# 06cpu_soc.net
KiCad netlist of a schematic drawn in Altium Designer
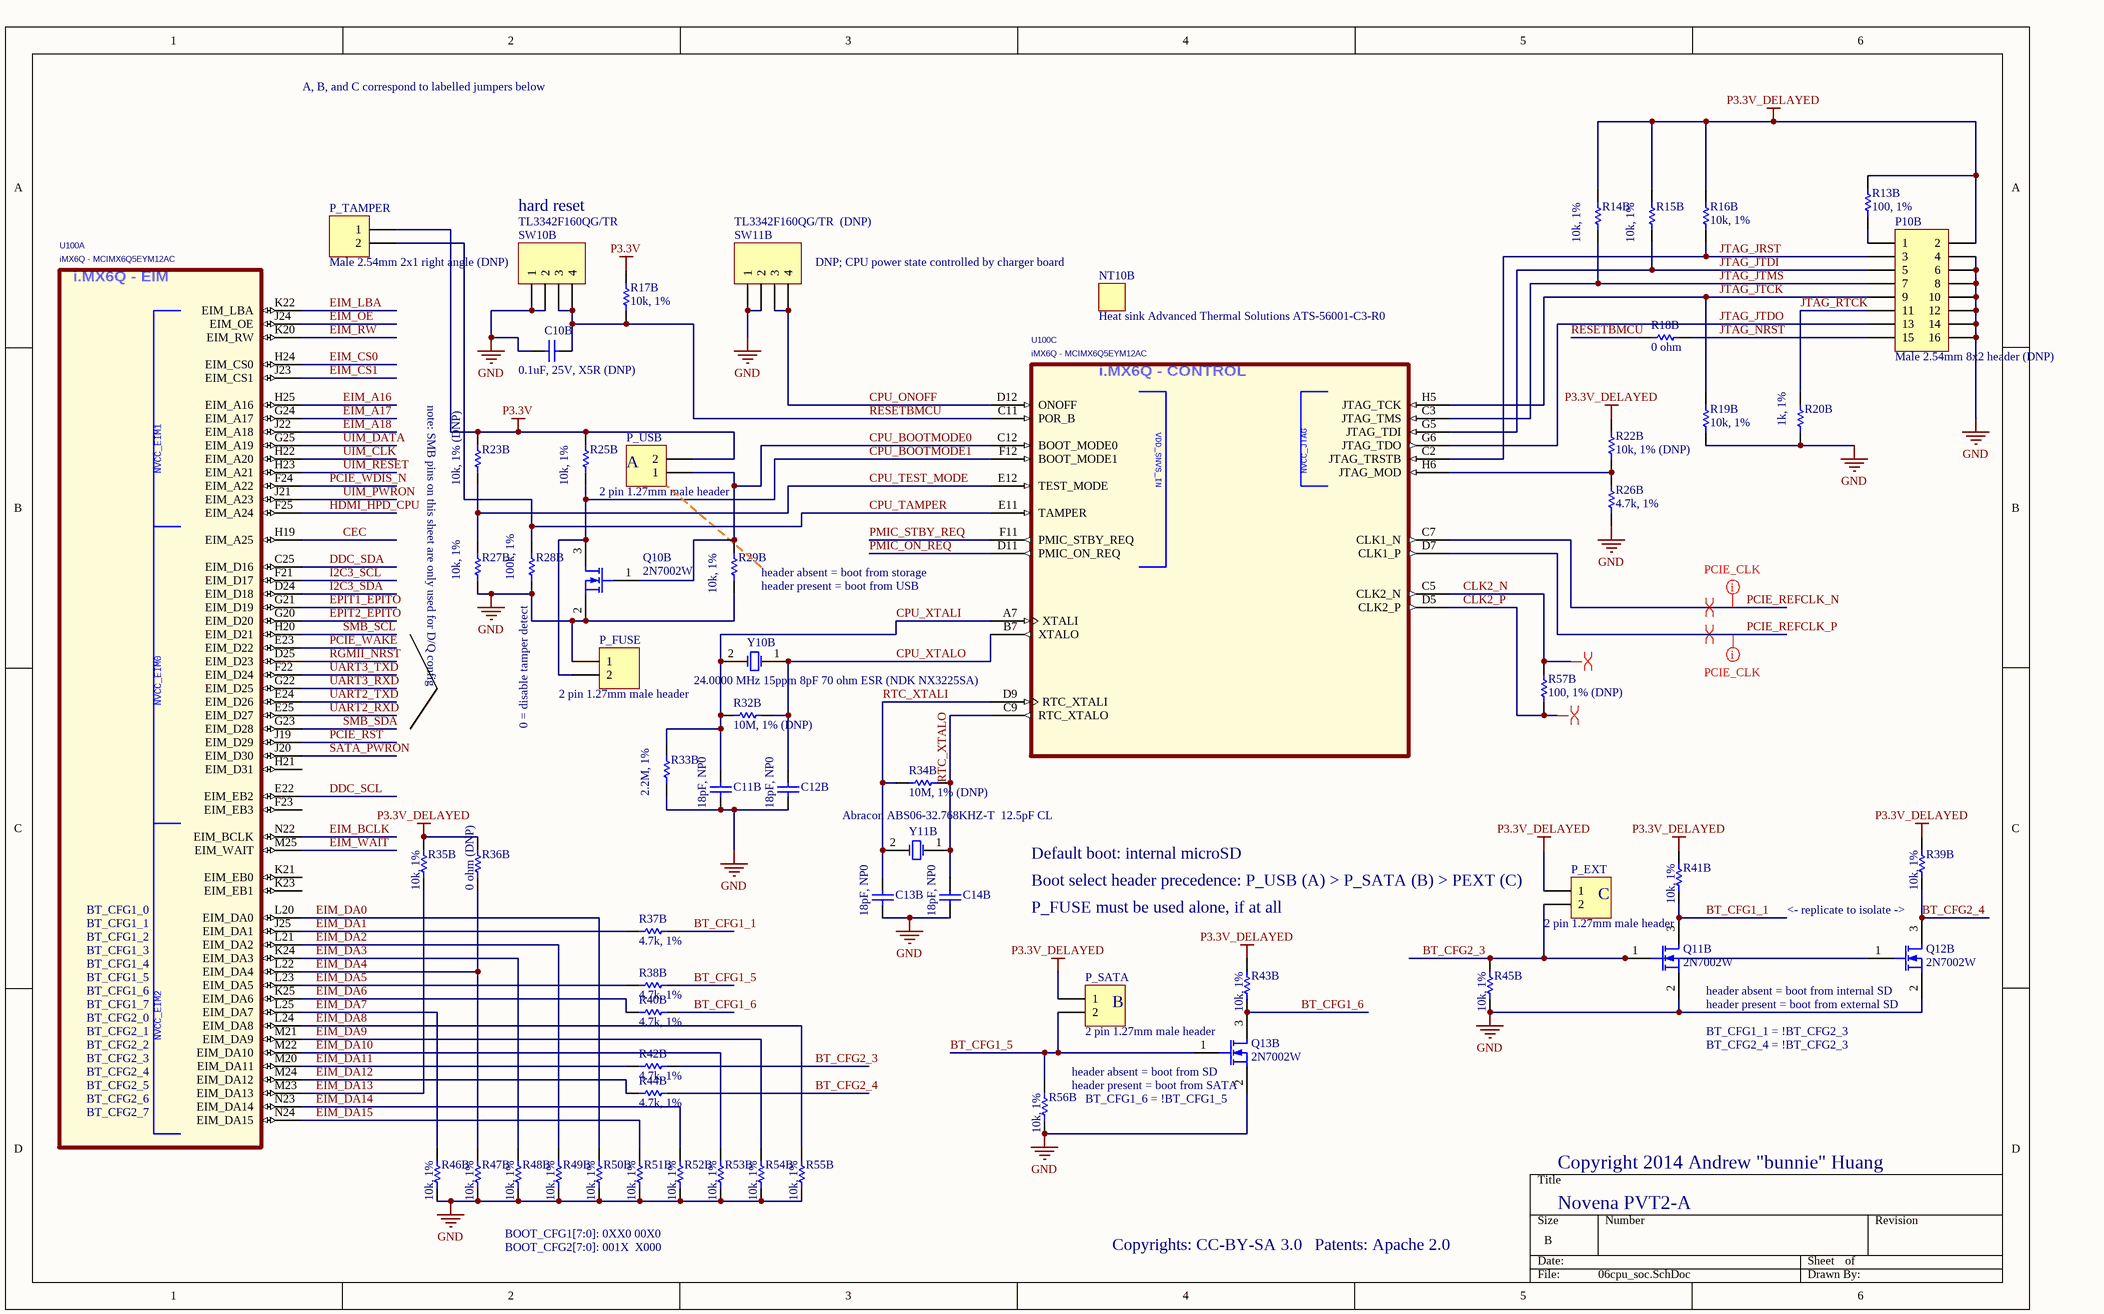
[diagram p0: 06cpu_soc.SchDoc]

(export (version "E")
  (design (tool "Eeschema 10.0.6"))
  (components
    (comp (ref "C10B")
      (value "0.1uF, 25V, X5R (DNP)")
      (footprint "CAPC1005N")
      (description "Capacitor (Semiconductor SIM Model)")
      (fields (field (name "PUBLISHER") "Altium Limited"))
      (libsource (lib "Miscellaneous Devices") (part "Cap Semi"))
    )
    (comp (ref "C11B")
      (value "18pF, NP0")
      (footprint "CAPC1005N")
      (description "Capacitor (Semiconductor SIM Model)")
      (fields (field (name "PUBLISHER") "Altium Limited"))
      (libsource (lib "Miscellaneous Devices") (part "Cap Semi"))
    )
    (comp (ref "C12B")
      (value "18pF, NP0")
      (footprint "CAPC1005N")
      (description "Capacitor (Semiconductor SIM Model)")
      (fields (field (name "PUBLISHER") "Altium Limited"))
      (libsource (lib "Miscellaneous Devices") (part "Cap Semi"))
    )
    (comp (ref "C13B")
      (value "18pF, NP0")
      (footprint "CAPC1005N")
      (description "Capacitor (Semiconductor SIM Model)")
      (fields (field (name "PUBLISHER") "Altium Limited"))
      (libsource (lib "Miscellaneous Devices") (part "Cap Semi"))
    )
    (comp (ref "C14B")
      (value "18pF, NP0")
      (footprint "CAPC1005N")
      (description "Capacitor (Semiconductor SIM Model)")
      (fields (field (name "PUBLISHER") "Altium Limited"))
      (libsource (lib "Miscellaneous Devices") (part "Cap Semi"))
    )
    (comp (ref "NT10B")
      (value "Heat sink Advanced Thermal Solutions ATS-56001-C3-R0")
      (description "Placeholder for non-electrical BOM items")
      (libsource (lib "commonsch") (part "NOTE"))
    )
    (comp (ref "P10B")
      (value "Male 2.54mm 8x2 header (DNP)")
      (footprint "HDR2X8")
      (description "Header, 8-Pin, Dual row")
      (fields (field (name "PUBLISHER") "Altium Limited"))
      (libsource (lib "Miscellaneous Connectors") (part "Header 8X2"))
    )
    (comp (ref "P_EXT")
      (value "2 pin 1.27mm male header")
      (footprint "HEADER_2_1.27MM")
      (description "Header, 2-Pin")
      (fields (field (name "PUBLISHER") "Altium Limited"))
      (libsource (lib "") (part "Header 2_1"))
    )
    (comp (ref "P_FUSE")
      (value "2 pin 1.27mm male header")
      (footprint "HEADER_2_1.27MM")
      (description "Header, 2-Pin")
      (fields (field (name "PUBLISHER") "Altium Limited"))
      (libsource (lib "") (part "Header 2_1"))
    )
    (comp (ref "P_SATA")
      (value "2 pin 1.27mm male header")
      (footprint "HEADER_2_1.27MM")
      (description "Header, 2-Pin")
      (fields (field (name "PUBLISHER") "Altium Limited"))
      (libsource (lib "") (part "Header 2_1"))
    )
    (comp (ref "P_TAMPER")
      (value "Male 2.54mm 2x1 right angle (DNP)")
      (footprint "HDR1X2H")
      (description "Header, 2-Pin, Right Angle")
      (fields (field (name "PUBLISHER") "Altium Limited"))
      (libsource (lib "Miscellaneous Connectors") (part "Header 2H"))
    )
    (comp (ref "P_USB")
      (value "2 pin 1.27mm male header")
      (footprint "HEADER_2_1.27MM")
      (description "Header, 2-Pin")
      (fields (field (name "PUBLISHER") "Altium Limited"))
      (libsource (lib "Miscellaneous Connectors") (part "Header 2"))
    )
    (comp (ref "Q10B")
      (value "2N7002W")
      (footprint "SOT323-3AN")
      (description "N-Channel MOSFET")
      (fields (field (name "PUBLISHER") "Altium Limited"))
      (libsource (lib "Miscellaneous Devices") (part "MOSFET-N"))
    )
    (comp (ref "Q11B")
      (value "2N7002W")
      (footprint "SOT323-3AN")
      (description "N-Channel MOSFET")
      (fields (field (name "PUBLISHER") "Altium Limited"))
      (libsource (lib "Miscellaneous Devices") (part "MOSFET-N"))
    )
    (comp (ref "Q12B")
      (value "2N7002W")
      (footprint "SOT323-3AN")
      (description "N-Channel MOSFET")
      (fields (field (name "PUBLISHER") "Altium Limited"))
      (libsource (lib "Miscellaneous Devices") (part "MOSFET-N"))
    )
    (comp (ref "Q13B")
      (value "2N7002W")
      (footprint "SOT323-3AN")
      (description "N-Channel MOSFET")
      (fields (field (name "PUBLISHER") "Altium Limited"))
      (libsource (lib "Miscellaneous Devices") (part "MOSFET-N"))
    )
    (comp (ref "R13B")
      (value "100, 1%")
      (footprint "RESC1005N")
      (description "Resistor")
      (fields (field (name "PUBLISHER") "Altium Limited"))
      (libsource (lib "Miscellaneous Devices") (part "Res1"))
    )
    (comp (ref "R14B")
      (value "10k, 1%")
      (footprint "RESC1005N")
      (description "Resistor")
      (fields (field (name "PUBLISHER") "Altium Limited"))
      (libsource (lib "Miscellaneous Devices") (part "Res1"))
    )
    (comp (ref "R15B")
      (value "10k, 1%")
      (footprint "RESC1005N")
      (description "Resistor")
      (fields (field (name "PUBLISHER") "Altium Limited"))
      (libsource (lib "Miscellaneous Devices") (part "Res1"))
    )
    (comp (ref "R16B")
      (value "10k, 1%")
      (footprint "RESC1005N")
      (description "Resistor")
      (fields (field (name "PUBLISHER") "Altium Limited"))
      (libsource (lib "Miscellaneous Devices") (part "Res1"))
    )
    (comp (ref "R17B")
      (value "10k, 1%")
      (footprint "RESC1005N")
      (description "Resistor")
      (fields (field (name "PUBLISHER") "Altium Limited"))
      (libsource (lib "Miscellaneous Devices") (part "Res1"))
    )
    (comp (ref "R18B")
      (value "0 ohm")
      (footprint "RESC1005N")
      (description "Resistor")
      (fields (field (name "PUBLISHER") "Altium Limited"))
      (libsource (lib "Miscellaneous Devices") (part "Res1"))
    )
    (comp (ref "R19B")
      (value "10k, 1%")
      (footprint "RESC1005N")
      (description "Resistor")
      (fields (field (name "PUBLISHER") "Altium Limited"))
      (libsource (lib "Miscellaneous Devices") (part "Res1"))
    )
    (comp (ref "R20B")
      (value "1k, 1%")
      (footprint "RESC1005N")
      (description "Resistor")
      (fields (field (name "PUBLISHER") "Altium Limited"))
      (libsource (lib "Miscellaneous Devices") (part "Res1"))
    )
    (comp (ref "R22B")
      (value "10k, 1% (DNP)")
      (footprint "RESC1005N")
      (description "Resistor")
      (fields (field (name "PUBLISHER") "Altium Limited"))
      (libsource (lib "Miscellaneous Devices") (part "Res1"))
    )
    (comp (ref "R23B")
      (value "10k, 1% (DNP)")
      (footprint "RESC1005N")
      (description "Resistor")
      (fields (field (name "PUBLISHER") "Altium Limited"))
      (libsource (lib "Miscellaneous Devices") (part "Res1"))
    )
    (comp (ref "R25B")
      (value "10k, 1%")
      (footprint "RESC1005N")
      (description "Resistor")
      (fields (field (name "PUBLISHER") "Altium Limited"))
      (libsource (lib "Miscellaneous Devices") (part "Res1"))
    )
    (comp (ref "R26B")
      (value "4.7k, 1%")
      (footprint "RESC1005N")
      (description "Resistor")
      (fields (field (name "PUBLISHER") "Altium Limited"))
      (libsource (lib "Miscellaneous Devices") (part "Res1"))
    )
    (comp (ref "R27B")
      (value "10k, 1%")
      (footprint "RESC1005N")
      (description "Resistor")
      (fields (field (name "PUBLISHER") "Altium Limited"))
      (libsource (lib "Miscellaneous Devices") (part "Res1"))
    )
    (comp (ref "R28B")
      (value "100k, 1%")
      (footprint "RESC1005N")
      (description "Resistor")
      (fields (field (name "PUBLISHER") "Altium Limited"))
      (libsource (lib "Miscellaneous Devices") (part "Res1"))
    )
    (comp (ref "R29B")
      (value "10k, 1%")
      (footprint "RESC1005N")
      (description "Resistor")
      (fields (field (name "PUBLISHER") "Altium Limited"))
      (libsource (lib "Miscellaneous Devices") (part "Res1"))
    )
    (comp (ref "R32B")
      (value "10M, 1% (DNP)")
      (footprint "RESC1005N")
      (description "Resistor")
      (fields (field (name "PUBLISHER") "Altium Limited"))
      (libsource (lib "Miscellaneous Devices") (part "Res1"))
    )
    (comp (ref "R33B")
      (value "2.2M, 1%")
      (footprint "RESC1005N")
      (description "Resistor")
      (fields (field (name "PUBLISHER") "Altium Limited"))
      (libsource (lib "Miscellaneous Devices") (part "Res1"))
    )
    (comp (ref "R34B")
      (value "10M, 1% (DNP)")
      (footprint "RESC1005N")
      (description "Resistor")
      (fields (field (name "PUBLISHER") "Altium Limited"))
      (libsource (lib "Miscellaneous Devices") (part "Res1"))
    )
    (comp (ref "R35B")
      (value "10k, 1%")
      (footprint "RESC1005N")
      (description "Resistor")
      (fields (field (name "PUBLISHER") "Altium Limited"))
      (libsource (lib "Miscellaneous Devices") (part "Res1"))
    )
    (comp (ref "R36B")
      (value "0 ohm (DNP)")
      (footprint "RESC1005N")
      (description "Resistor")
      (fields (field (name "PUBLISHER") "Altium Limited"))
      (libsource (lib "Miscellaneous Devices") (part "Res1"))
    )
    (comp (ref "R37B")
      (value "4.7k, 1%")
      (footprint "RESC1005N")
      (description "Resistor")
      (fields (field (name "PUBLISHER") "Altium Limited"))
      (libsource (lib "Miscellaneous Devices") (part "Res1"))
    )
    (comp (ref "R38B")
      (value "4.7k, 1%")
      (footprint "RESC1005N")
      (description "Resistor")
      (fields (field (name "PUBLISHER") "Altium Limited"))
      (libsource (lib "Miscellaneous Devices") (part "Res1"))
    )
    (comp (ref "R39B")
      (value "10k, 1%")
      (footprint "RESC1005N")
      (description "Resistor")
      (fields (field (name "PUBLISHER") "Altium Limited"))
      (libsource (lib "Miscellaneous Devices") (part "Res1"))
    )
    (comp (ref "R40B")
      (value "4.7k, 1%")
      (footprint "RESC1005N")
      (description "Resistor")
      (fields (field (name "PUBLISHER") "Altium Limited"))
      (libsource (lib "Miscellaneous Devices") (part "Res1"))
    )
    (comp (ref "R41B")
      (value "10k, 1%")
      (footprint "RESC1005N")
      (description "Resistor")
      (fields (field (name "PUBLISHER") "Altium Limited"))
      (libsource (lib "Miscellaneous Devices") (part "Res1"))
    )
    (comp (ref "R42B")
      (value "4.7k, 1%")
      (footprint "RESC1005N")
      (description "Resistor")
      (fields (field (name "PUBLISHER") "Altium Limited"))
      (libsource (lib "Miscellaneous Devices") (part "Res1"))
    )
    (comp (ref "R43B")
      (value "10k, 1%")
      (footprint "RESC1005N")
      (description "Resistor")
      (fields (field (name "PUBLISHER") "Altium Limited"))
      (libsource (lib "Miscellaneous Devices") (part "Res1"))
    )
    (comp (ref "R44B")
      (value "4.7k, 1%")
      (footprint "RESC1005N")
      (description "Resistor")
      (fields (field (name "PUBLISHER") "Altium Limited"))
      (libsource (lib "Miscellaneous Devices") (part "Res1"))
    )
    (comp (ref "R45B")
      (value "10k, 1%")
      (footprint "RESC1005N")
      (description "Resistor")
      (fields (field (name "PUBLISHER") "Altium Limited"))
      (libsource (lib "Miscellaneous Devices") (part "Res1"))
    )
    (comp (ref "R46B")
      (value "10k, 1%")
      (footprint "RESC1005N")
      (description "Resistor")
      (fields (field (name "PUBLISHER") "Altium Limited"))
      (libsource (lib "Miscellaneous Devices") (part "Res1"))
    )
    (comp (ref "R47B")
      (value "10k, 1%")
      (footprint "RESC1005N")
      (description "Resistor")
      (fields (field (name "PUBLISHER") "Altium Limited"))
      (libsource (lib "Miscellaneous Devices") (part "Res1"))
    )
    (comp (ref "R48B")
      (value "10k, 1%")
      (footprint "RESC1005N")
      (description "Resistor")
      (fields (field (name "PUBLISHER") "Altium Limited"))
      (libsource (lib "Miscellaneous Devices") (part "Res1"))
    )
    (comp (ref "R49B")
      (value "10k, 1%")
      (footprint "RESC1005N")
      (description "Resistor")
      (fields (field (name "PUBLISHER") "Altium Limited"))
      (libsource (lib "Miscellaneous Devices") (part "Res1"))
    )
    (comp (ref "R50B")
      (value "10k, 1%")
      (footprint "RESC1005N")
      (description "Resistor")
      (fields (field (name "PUBLISHER") "Altium Limited"))
      (libsource (lib "Miscellaneous Devices") (part "Res1"))
    )
    (comp (ref "R51B")
      (value "10k, 1%")
      (footprint "RESC1005N")
      (description "Resistor")
      (fields (field (name "PUBLISHER") "Altium Limited"))
      (libsource (lib "Miscellaneous Devices") (part "Res1"))
    )
    (comp (ref "R52B")
      (value "10k, 1%")
      (footprint "RESC1005N")
      (description "Resistor")
      (fields (field (name "PUBLISHER") "Altium Limited"))
      (libsource (lib "Miscellaneous Devices") (part "Res1"))
    )
    (comp (ref "R53B")
      (value "10k, 1%")
      (footprint "RESC1005N")
      (description "Resistor")
      (fields (field (name "PUBLISHER") "Altium Limited"))
      (libsource (lib "Miscellaneous Devices") (part "Res1"))
    )
    (comp (ref "R54B")
      (value "10k, 1%")
      (footprint "RESC1005N")
      (description "Resistor")
      (fields (field (name "PUBLISHER") "Altium Limited"))
      (libsource (lib "Miscellaneous Devices") (part "Res1"))
    )
    (comp (ref "R55B")
      (value "10k, 1%")
      (footprint "RESC1005N")
      (description "Resistor")
      (fields (field (name "PUBLISHER") "Altium Limited"))
      (libsource (lib "Miscellaneous Devices") (part "Res1"))
    )
    (comp (ref "R56B")
      (value "10k, 1%")
      (footprint "RESC1005N")
      (description "Resistor")
      (fields (field (name "PUBLISHER") "Altium Limited"))
      (libsource (lib "Miscellaneous Devices") (part "Res1"))
    )
    (comp (ref "R57B")
      (value "100, 1% (DNP)")
      (footprint "RESC1005N")
      (description "Resistor")
      (fields (field (name "PUBLISHER") "Altium Limited"))
      (libsource (lib "Miscellaneous Devices") (part "Res1"))
    )
    (comp (ref "SW10B")
      (value "TL3342F160QG/TR")
      (footprint "SWITCH_TS-1187A")
      (description "Chi Fung TS-1187A")
      (fields (field (name "PUBLISHER") "Altium Limited"))
      (libsource (lib "Miscellaneous Connectors") (part "Header 4"))
    )
    (comp (ref "SW11B")
      (value "TL3342F160QG/TR  (DNP)")
      (footprint "SWITCH_TS-1187A")
      (description "Chi Fung TS-1187A")
      (fields (field (name "PUBLISHER") "Altium Limited"))
      (libsource (lib "Miscellaneous Connectors") (part "Header 4"))
    )
    (comp (ref "U100")
      (value "iMX6Q - MCIMX6Q5EYM12AC")
      (description "PCIMX6Q5EVT10AC")
      (libsource (lib "*") (part "PCIMX6Q6VV1A"))
    )
    (comp (ref "Y10B")
      (value "24.0000 MHz 15ppm 8pF 70 ohm ESR (NDK NX3225SA)")
      (footprint "NDK_NX3225SA")
      (description "Crystal Oscillator")
      (fields (field (name "PUBLISHER") "Altium Limited"))
      (libsource (lib "Miscellaneous Devices") (part "XTAL"))
    )
    (comp (ref "Y11B")
      (value "Abracon ABS06-32.768KHZ-T  12.5pF CL")
      (footprint "ABS06")
      (description "Crystal Oscillator")
      (fields (field (name "PUBLISHER") "Altium Limited"))
      (libsource (lib "Miscellaneous Devices") (part "XTAL"))
    )
  )
  (nets
    (net (code "1") (name "/BT_CFG1_1") (class "Default")
      (node (ref "Q11B") (pin "3") (pinfunction "D_3") (pintype "passive"))
      (node (ref "R37B") (pin "2") (pinfunction "2_2") (pintype "passive"))
      (node (ref "R41B") (pin "2") (pinfunction "2_2") (pintype "passive"))
    )
    (net (code "2") (name "/BT_CFG1_5") (class "Default")
      (node (ref "P_SATA") (pin "2") (pinfunction "2_2") (pintype "passive"))
      (node (ref "Q13B") (pin "1") (pinfunction "G_1") (pintype "passive"))
      (node (ref "R38B") (pin "2") (pinfunction "2_2") (pintype "passive"))
      (node (ref "R56B") (pin "1") (pinfunction "1_1") (pintype "passive"))
    )
    (net (code "3") (name "/BT_CFG1_6") (class "Default")
      (node (ref "Q13B") (pin "3") (pinfunction "D_3") (pintype "passive"))
      (node (ref "R40B") (pin "2") (pinfunction "2_2") (pintype "passive"))
      (node (ref "R43B") (pin "2") (pinfunction "2_2") (pintype "passive"))
    )
    (net (code "4") (name "/BT_CFG2_3") (class "Default")
      (node (ref "P_EXT") (pin "2") (pinfunction "2_2") (pintype "passive"))
      (node (ref "Q11B") (pin "1") (pinfunction "G_1") (pintype "passive"))
      (node (ref "Q12B") (pin "1") (pinfunction "G_1") (pintype "passive"))
      (node (ref "R42B") (pin "2") (pinfunction "2_2") (pintype "passive"))
      (node (ref "R45B") (pin "1") (pinfunction "1_1") (pintype "passive"))
    )
    (net (code "5") (name "/BT_CFG2_4") (class "Default")
      (node (ref "Q12B") (pin "3") (pinfunction "D_3") (pintype "passive"))
      (node (ref "R39B") (pin "2") (pinfunction "2_2") (pintype "passive"))
      (node (ref "R44B") (pin "2") (pinfunction "2_2") (pintype "passive"))
    )
    (net (code "6") (name "/CEC") (class "Default")
      (node (ref "U100") (pin "H19") (pinfunction "EIM_A25_H19") (pintype "bidirectional"))
    )
    (net (code "7") (name "/CLK2_N") (class "Default")
      (node (ref "R57B") (pin "2") (pinfunction "2_2") (pintype "passive"))
      (node (ref "U100") (pin "C5") (pinfunction "CLK2_N_C5") (pintype "output"))
    )
    (net (code "8") (name "/CLK2_P") (class "Default")
      (node (ref "R57B") (pin "1") (pinfunction "1_1") (pintype "passive"))
      (node (ref "U100") (pin "D5") (pinfunction "CLK2_P_D5") (pintype "output"))
    )
    (net (code "9") (name "/CPU_BOOTMODE0") (class "Default")
      (node (ref "P_USB") (pin "1") (pinfunction "1_1") (pintype "passive"))
      (node (ref "Q10B") (pin "1") (pinfunction "G_1") (pintype "passive"))
      (node (ref "R29B") (pin "2") (pinfunction "2_2") (pintype "passive"))
      (node (ref "U100") (pin "C12") (pinfunction "BOOT_MODE0_C12") (pintype "input"))
    )
    (net (code "10") (name "/CPU_BOOTMODE1") (class "Default")
      (node (ref "P_FUSE") (pin "2") (pinfunction "2_2") (pintype "passive"))
      (node (ref "Q10B") (pin "3") (pinfunction "D_3") (pintype "passive"))
      (node (ref "R25B") (pin "1") (pinfunction "1_1") (pintype "passive"))
      (node (ref "U100") (pin "F12") (pinfunction "BOOT_MODE1_F12") (pintype "input"))
    )
    (net (code "11") (name "/CPU_ONOFF") (class "Default")
      (node (ref "SW11B") (pin "3") (pinfunction "3_3") (pintype "passive"))
      (node (ref "SW11B") (pin "4") (pinfunction "4_4") (pintype "passive"))
      (node (ref "U100") (pin "D12") (pinfunction "ONOFF_D12") (pintype "input"))
    )
    (net (code "12") (name "/CPU_TAMPER") (class "Default")
      (node (ref "P_TAMPER") (pin "2") (pinfunction "2_2") (pintype "passive"))
      (node (ref "R28B") (pin "2") (pinfunction "2_2") (pintype "passive"))
      (node (ref "U100") (pin "E11") (pinfunction "TAMPER_E11") (pintype "input"))
    )
    (net (code "13") (name "/CPU_TEST_MODE") (class "Default")
      (node (ref "R23B") (pin "1") (pinfunction "1_1") (pintype "passive"))
      (node (ref "R27B") (pin "2") (pinfunction "2_2") (pintype "passive"))
      (node (ref "U100") (pin "E12") (pinfunction "TEST_MODE_E12") (pintype "input"))
    )
    (net (code "14") (name "/CPU_XTALI") (class "Default")
      (node (ref "C11B") (pin "1") (pinfunction "1_1") (pintype "passive"))
      (node (ref "R32B") (pin "1") (pinfunction "1_1") (pintype "passive"))
      (node (ref "R33B") (pin "1") (pinfunction "1_1") (pintype "passive"))
      (node (ref "U100") (pin "A7") (pinfunction "XTALI_A7") (pintype "input"))
      (node (ref "Y10B") (pin "2") (pinfunction "OSC2_2") (pintype "passive"))
    )
    (net (code "15") (name "/CPU_XTALO") (class "Default")
      (node (ref "C12B") (pin "1") (pinfunction "1_1") (pintype "passive"))
      (node (ref "R32B") (pin "2") (pinfunction "2_2") (pintype "passive"))
      (node (ref "U100") (pin "B7") (pinfunction "XTALO_B7") (pintype "output"))
      (node (ref "Y10B") (pin "1") (pinfunction "OSC1_1") (pintype "passive"))
    )
    (net (code "16") (name "/DDC_SCL") (class "Default")
      (node (ref "U100") (pin "E22") (pinfunction "EIM_EB2_E22") (pintype "bidirectional"))
    )
    (net (code "17") (name "/DDC_SDA") (class "Default")
      (node (ref "U100") (pin "C25") (pinfunction "EIM_D16_C25") (pintype "bidirectional"))
    )
    (net (code "18") (name "/EIM_A16") (class "Default")
      (node (ref "U100") (pin "H25") (pinfunction "EIM_A16_H25") (pintype "bidirectional"))
    )
    (net (code "19") (name "/EIM_A17") (class "Default")
      (node (ref "U100") (pin "G24") (pinfunction "EIM_A17_G24") (pintype "bidirectional"))
    )
    (net (code "20") (name "/EIM_A18") (class "Default")
      (node (ref "U100") (pin "J22") (pinfunction "EIM_A18_J22") (pintype "bidirectional"))
    )
    (net (code "21") (name "/EIM_BCLK") (class "Default")
      (node (ref "U100") (pin "N22") (pinfunction "EIM_BCLK_N22") (pintype "bidirectional"))
    )
    (net (code "22") (name "/EIM_CS0") (class "Default")
      (node (ref "U100") (pin "H24") (pinfunction "EIM_CS0_H24") (pintype "bidirectional"))
    )
    (net (code "23") (name "/EIM_CS1") (class "Default")
      (node (ref "U100") (pin "J23") (pinfunction "EIM_CS1_J23") (pintype "bidirectional"))
    )
    (net (code "24") (name "/EIM_DA0") (class "Default")
      (node (ref "R50B") (pin "1") (pinfunction "1_1") (pintype "passive"))
      (node (ref "U100") (pin "L20") (pinfunction "EIM_DA0_L20") (pintype "bidirectional"))
    )
    (net (code "25") (name "/EIM_DA1") (class "Default")
      (node (ref "R37B") (pin "1") (pinfunction "1_1") (pintype "passive"))
      (node (ref "U100") (pin "J25") (pinfunction "EIM_DA1_J25") (pintype "bidirectional"))
    )
    (net (code "26") (name "/EIM_DA2") (class "Default")
      (node (ref "R49B") (pin "1") (pinfunction "1_1") (pintype "passive"))
      (node (ref "U100") (pin "L21") (pinfunction "EIM_DA2_L21") (pintype "bidirectional"))
    )
    (net (code "27") (name "/EIM_DA3") (class "Default")
      (node (ref "R48B") (pin "1") (pinfunction "1_1") (pintype "passive"))
      (node (ref "U100") (pin "K24") (pinfunction "EIM_DA3_K24") (pintype "bidirectional"))
    )
    (net (code "28") (name "/EIM_DA4") (class "Default")
      (node (ref "R36B") (pin "2") (pinfunction "2_2") (pintype "passive"))
      (node (ref "R47B") (pin "1") (pinfunction "1_1") (pintype "passive"))
      (node (ref "U100") (pin "L22") (pinfunction "EIM_DA4_L22") (pintype "bidirectional"))
    )
    (net (code "29") (name "/EIM_DA5") (class "Default")
      (node (ref "R38B") (pin "1") (pinfunction "1_1") (pintype "passive"))
      (node (ref "U100") (pin "L23") (pinfunction "EIM_DA5_L23") (pintype "bidirectional"))
    )
    (net (code "30") (name "/EIM_DA6") (class "Default")
      (node (ref "R40B") (pin "1") (pinfunction "1_1") (pintype "passive"))
      (node (ref "U100") (pin "K25") (pinfunction "EIM_DA6_K25") (pintype "bidirectional"))
    )
    (net (code "31") (name "/EIM_DA7") (class "Default")
      (node (ref "R46B") (pin "1") (pinfunction "1_1") (pintype "passive"))
      (node (ref "U100") (pin "L25") (pinfunction "EIM_DA7_L25") (pintype "bidirectional"))
    )
    (net (code "32") (name "/EIM_DA8") (class "Default")
      (node (ref "R55B") (pin "1") (pinfunction "1_1") (pintype "passive"))
      (node (ref "U100") (pin "L24") (pinfunction "EIM_DA8_L24") (pintype "bidirectional"))
    )
    (net (code "33") (name "/EIM_DA9") (class "Default")
      (node (ref "R54B") (pin "1") (pinfunction "1_1") (pintype "passive"))
      (node (ref "U100") (pin "M21") (pinfunction "EIM_DA9_M21") (pintype "bidirectional"))
    )
    (net (code "34") (name "/EIM_DA10") (class "Default")
      (node (ref "R53B") (pin "1") (pinfunction "1_1") (pintype "passive"))
      (node (ref "U100") (pin "M22") (pinfunction "EIM_DA10_M22") (pintype "bidirectional"))
    )
    (net (code "35") (name "/EIM_DA11") (class "Default")
      (node (ref "R42B") (pin "1") (pinfunction "1_1") (pintype "passive"))
      (node (ref "U100") (pin "M20") (pinfunction "EIM_DA11_M20") (pintype "bidirectional"))
    )
    (net (code "36") (name "/EIM_DA12") (class "Default")
      (node (ref "R44B") (pin "1") (pinfunction "1_1") (pintype "passive"))
      (node (ref "U100") (pin "M24") (pinfunction "EIM_DA12_M24") (pintype "bidirectional"))
    )
    (net (code "37") (name "/EIM_DA13") (class "Default")
      (node (ref "R35B") (pin "2") (pinfunction "2_2") (pintype "passive"))
      (node (ref "U100") (pin "M23") (pinfunction "EIM_DA13_M23") (pintype "bidirectional"))
    )
    (net (code "38") (name "/EIM_DA14") (class "Default")
      (node (ref "R52B") (pin "1") (pinfunction "1_1") (pintype "passive"))
      (node (ref "U100") (pin "N23") (pinfunction "EIM_DA14_N23") (pintype "bidirectional"))
    )
    (net (code "39") (name "/EIM_DA15") (class "Default")
      (node (ref "R51B") (pin "1") (pinfunction "1_1") (pintype "passive"))
      (node (ref "U100") (pin "N24") (pinfunction "EIM_DA15_N24") (pintype "bidirectional"))
    )
    (net (code "40") (name "/EIM_LBA") (class "Default")
      (node (ref "U100") (pin "K22") (pinfunction "EIM_LBA_K22") (pintype "bidirectional"))
    )
    (net (code "41") (name "/EIM_OE") (class "Default")
      (node (ref "U100") (pin "J24") (pinfunction "EIM_OE_J24") (pintype "bidirectional"))
    )
    (net (code "42") (name "/EIM_RW") (class "Default")
      (node (ref "U100") (pin "K20") (pinfunction "EIM_RW_K20") (pintype "bidirectional"))
    )
    (net (code "43") (name "/EIM_WAIT") (class "Default")
      (node (ref "U100") (pin "M25") (pinfunction "EIM_WAIT_M25") (pintype "bidirectional"))
    )
    (net (code "44") (name "/EPIT1_EPITO") (class "Default")
      (node (ref "U100") (pin "G21") (pinfunction "EIM_D19_G21") (pintype "bidirectional"))
    )
    (net (code "45") (name "/EPIT2_EPITO") (class "Default")
      (node (ref "U100") (pin "G20") (pinfunction "EIM_D20_G20") (pintype "bidirectional"))
    )
    (net (code "46") (name "/HDMI_HPD_CPU") (class "Default")
      (node (ref "U100") (pin "F25") (pinfunction "EIM_A24_F25") (pintype "bidirectional"))
    )
    (net (code "47") (name "/I2C3_SCL") (class "Default")
      (node (ref "U100") (pin "F21") (pinfunction "EIM_D17_F21") (pintype "bidirectional"))
    )
    (net (code "48") (name "/I2C3_SDA") (class "Default")
      (node (ref "U100") (pin "D24") (pinfunction "EIM_D18_D24") (pintype "bidirectional"))
    )
    (net (code "49") (name "/JTAG_JRST") (class "Default")
      (node (ref "P10B") (pin "3") (pinfunction "3_3") (pintype "passive"))
      (node (ref "R16B") (pin "1") (pinfunction "1_1") (pintype "passive"))
      (node (ref "U100") (pin "C2") (pinfunction "JTAG_TRSTB_C2") (pintype "input"))
    )
    (net (code "50") (name "/JTAG_JTCK") (class "Default")
      (node (ref "P10B") (pin "9") (pinfunction "9_9") (pintype "passive"))
      (node (ref "R19B") (pin "2") (pinfunction "2_2") (pintype "passive"))
      (node (ref "U100") (pin "H5") (pinfunction "JTAG_TCK_H5") (pintype "input"))
    )
    (net (code "51") (name "/JTAG_JTDI") (class "Default")
      (node (ref "P10B") (pin "5") (pinfunction "5_5") (pintype "passive"))
      (node (ref "R15B") (pin "1") (pinfunction "1_1") (pintype "passive"))
      (node (ref "U100") (pin "G5") (pinfunction "JTAG_TDI_G5") (pintype "input"))
    )
    (net (code "52") (name "/JTAG_JTDO") (class "Default")
      (node (ref "P10B") (pin "13") (pinfunction "13_13") (pintype "passive"))
      (node (ref "U100") (pin "G6") (pinfunction "JTAG_TDO_G6") (pintype "output"))
    )
    (net (code "53") (name "/JTAG_JTMS") (class "Default")
      (node (ref "P10B") (pin "7") (pinfunction "7_7") (pintype "passive"))
      (node (ref "R14B") (pin "1") (pinfunction "1_1") (pintype "passive"))
      (node (ref "U100") (pin "C3") (pinfunction "JTAG_TMS_C3") (pintype "input"))
    )
    (net (code "54") (name "/JTAG_NRST") (class "Default")
      (node (ref "P10B") (pin "15") (pinfunction "15_15") (pintype "passive"))
      (node (ref "R18B") (pin "1") (pinfunction "1_1") (pintype "passive"))
    )
    (net (code "55") (name "/JTAG_RTCK") (class "Default")
      (node (ref "P10B") (pin "11") (pinfunction "11_11") (pintype "passive"))
      (node (ref "R20B") (pin "2") (pinfunction "2_2") (pintype "passive"))
    )
    (net (code "56") (name "/PCIE_REFCLK_N") (class "Default")
      (node (ref "U100") (pin "C7") (pinfunction "CLK1_N_C7") (pintype "output"))
    )
    (net (code "57") (name "/PCIE_REFCLK_P") (class "Default")
      (node (ref "U100") (pin "D7") (pinfunction "CLK1_P_D7") (pintype "output"))
    )
    (net (code "58") (name "/PCIE_RST") (class "Default")
      (node (ref "U100") (pin "J19") (pinfunction "EIM_D29_J19") (pintype "bidirectional"))
    )
    (net (code "59") (name "/PCIE_WAKE") (class "Default")
      (node (ref "U100") (pin "E23") (pinfunction "EIM_D22_E23") (pintype "bidirectional"))
    )
    (net (code "60") (name "/PCIE_WDIS_N") (class "Default")
      (node (ref "U100") (pin "F24") (pinfunction "EIM_A22_F24") (pintype "bidirectional"))
    )
    (net (code "61") (name "/PMIC_ON_REQ") (class "Default")
      (node (ref "U100") (pin "D11") (pinfunction "PMIC_ON_REQ_D11") (pintype "output"))
    )
    (net (code "62") (name "/PMIC_STBY_REQ") (class "Default")
      (node (ref "U100") (pin "F11") (pinfunction "PMIC_STBY_REQ_F11") (pintype "output"))
    )
    (net (code "63") (name "/RESETBMCU") (class "Default")
      (node (ref "C10B") (pin "1") (pinfunction "1_1") (pintype "passive"))
      (node (ref "R17B") (pin "1") (pinfunction "1_1") (pintype "passive"))
      (node (ref "R18B") (pin "2") (pinfunction "2_2") (pintype "passive"))
      (node (ref "SW10B") (pin "3") (pinfunction "3_3") (pintype "passive"))
      (node (ref "SW10B") (pin "4") (pinfunction "4_4") (pintype "passive"))
      (node (ref "U100") (pin "C11") (pinfunction "POR_B_C11") (pintype "input"))
    )
    (net (code "64") (name "/RGMII_NRST") (class "Default")
      (node (ref "U100") (pin "D25") (pinfunction "EIM_D23_D25") (pintype "bidirectional"))
    )
    (net (code "65") (name "/RTC_XTALI") (class "Default")
      (node (ref "C13B") (pin "1") (pinfunction "1_1") (pintype "passive"))
      (node (ref "R34B") (pin "1") (pinfunction "1_1") (pintype "passive"))
      (node (ref "U100") (pin "D9") (pinfunction "RTC_XTALI_D9") (pintype "input"))
      (node (ref "Y11B") (pin "2") (pinfunction "OSC2_2") (pintype "passive"))
    )
    (net (code "66") (name "/RTC_XTALO") (class "Default")
      (node (ref "C14B") (pin "1") (pinfunction "1_1") (pintype "passive"))
      (node (ref "R34B") (pin "2") (pinfunction "2_2") (pintype "passive"))
      (node (ref "U100") (pin "C9") (pinfunction "RTC_XTALO_C9") (pintype "output"))
      (node (ref "Y11B") (pin "1") (pinfunction "OSC1_1") (pintype "passive"))
    )
    (net (code "67") (name "/SATA_PWRON") (class "Default")
      (node (ref "U100") (pin "J20") (pinfunction "EIM_D30_J20") (pintype "bidirectional"))
    )
    (net (code "68") (name "/SMB_SCL") (class "Default")
      (node (ref "U100") (pin "H20") (pinfunction "EIM_D21_H20") (pintype "bidirectional"))
    )
    (net (code "69") (name "/SMB_SDA") (class "Default")
      (node (ref "U100") (pin "G23") (pinfunction "EIM_D28_G23") (pintype "bidirectional"))
    )
    (net (code "70") (name "/UART2_RXD") (class "Default")
      (node (ref "U100") (pin "E25") (pinfunction "EIM_D27_E25") (pintype "bidirectional"))
    )
    (net (code "71") (name "/UART2_TXD") (class "Default")
      (node (ref "U100") (pin "E24") (pinfunction "EIM_D26_E24") (pintype "bidirectional"))
    )
    (net (code "72") (name "/UART3_RXD") (class "Default")
      (node (ref "U100") (pin "G22") (pinfunction "EIM_D25_G22") (pintype "bidirectional"))
    )
    (net (code "73") (name "/UART3_TXD") (class "Default")
      (node (ref "U100") (pin "F22") (pinfunction "EIM_D24_F22") (pintype "bidirectional"))
    )
    (net (code "74") (name "/UIM_CLK") (class "Default")
      (node (ref "U100") (pin "H22") (pinfunction "EIM_A20_H22") (pintype "bidirectional"))
    )
    (net (code "75") (name "/UIM_DATA") (class "Default")
      (node (ref "U100") (pin "G25") (pinfunction "EIM_A19_G25") (pintype "bidirectional"))
    )
    (net (code "76") (name "/UIM_PWRON") (class "Default")
      (node (ref "U100") (pin "J21") (pinfunction "EIM_A23_J21") (pintype "bidirectional"))
    )
    (net (code "77") (name "/UIM_RESET") (class "Default")
      (node (ref "U100") (pin "H23") (pinfunction "EIM_A21_H23") (pintype "bidirectional"))
    )
    (net (code "78") (name "GND") (class "Default")
      (node (ref "C10B") (pin "2") (pinfunction "2_2") (pintype "passive"))
      (node (ref "C11B") (pin "2") (pinfunction "2_2") (pintype "passive"))
      (node (ref "C12B") (pin "2") (pinfunction "2_2") (pintype "passive"))
      (node (ref "C13B") (pin "2") (pinfunction "2_2") (pintype "passive"))
      (node (ref "C14B") (pin "2") (pinfunction "2_2") (pintype "passive"))
      (node (ref "P10B") (pin "10") (pinfunction "10_10") (pintype "passive"))
      (node (ref "P10B") (pin "12") (pinfunction "12_12") (pintype "passive"))
      (node (ref "P10B") (pin "14") (pinfunction "14_14") (pintype "passive"))
      (node (ref "P10B") (pin "16") (pinfunction "16_16") (pintype "passive"))
      (node (ref "P10B") (pin "4") (pinfunction "4_4") (pintype "passive"))
      (node (ref "P10B") (pin "6") (pinfunction "6_6") (pintype "passive"))
      (node (ref "P10B") (pin "8") (pinfunction "8_8") (pintype "passive"))
      (node (ref "P_FUSE") (pin "1") (pinfunction "1_1") (pintype "passive"))
      (node (ref "Q10B") (pin "2") (pinfunction "S_2") (pintype "passive"))
      (node (ref "Q11B") (pin "2") (pinfunction "S_2") (pintype "passive"))
      (node (ref "Q12B") (pin "2") (pinfunction "S_2") (pintype "passive"))
      (node (ref "Q13B") (pin "2") (pinfunction "S_2") (pintype "passive"))
      (node (ref "R19B") (pin "1") (pinfunction "1_1") (pintype "passive"))
      (node (ref "R20B") (pin "1") (pinfunction "1_1") (pintype "passive"))
      (node (ref "R26B") (pin "1") (pinfunction "1_1") (pintype "passive"))
      (node (ref "R27B") (pin "1") (pinfunction "1_1") (pintype "passive"))
      (node (ref "R28B") (pin "1") (pinfunction "1_1") (pintype "passive"))
      (node (ref "R29B") (pin "1") (pinfunction "1_1") (pintype "passive"))
      (node (ref "R33B") (pin "2") (pinfunction "2_2") (pintype "passive"))
      (node (ref "R45B") (pin "2") (pinfunction "2_2") (pintype "passive"))
      (node (ref "R46B") (pin "2") (pinfunction "2_2") (pintype "passive"))
      (node (ref "R47B") (pin "2") (pinfunction "2_2") (pintype "passive"))
      (node (ref "R48B") (pin "2") (pinfunction "2_2") (pintype "passive"))
      (node (ref "R49B") (pin "2") (pinfunction "2_2") (pintype "passive"))
      (node (ref "R50B") (pin "2") (pinfunction "2_2") (pintype "passive"))
      (node (ref "R51B") (pin "2") (pinfunction "2_2") (pintype "passive"))
      (node (ref "R52B") (pin "2") (pinfunction "2_2") (pintype "passive"))
      (node (ref "R53B") (pin "2") (pinfunction "2_2") (pintype "passive"))
      (node (ref "R54B") (pin "2") (pinfunction "2_2") (pintype "passive"))
      (node (ref "R55B") (pin "2") (pinfunction "2_2") (pintype "passive"))
      (node (ref "R56B") (pin "2") (pinfunction "2_2") (pintype "passive"))
      (node (ref "SW10B") (pin "1") (pinfunction "1_1") (pintype "passive"))
      (node (ref "SW10B") (pin "2") (pinfunction "2_2") (pintype "passive"))
      (node (ref "SW11B") (pin "1") (pinfunction "1_1") (pintype "passive"))
      (node (ref "SW11B") (pin "2") (pinfunction "2_2") (pintype "passive"))
    )
    (net (code "79") (name "Net-(P10B-Pad1)") (class "Default")
      (node (ref "P10B") (pin "1") (pinfunction "1_1") (pintype "passive"))
      (node (ref "R13B") (pin "1") (pinfunction "1_1") (pintype "passive"))
    )
    (net (code "80") (name "Net-(U100C-JTAG_MOD)") (class "Default")
      (node (ref "R22B") (pin "1") (pinfunction "1_1") (pintype "passive"))
      (node (ref "R26B") (pin "2") (pinfunction "2_2") (pintype "passive"))
      (node (ref "U100") (pin "H6") (pinfunction "JTAG_MOD_H6") (pintype "input"))
    )
    (net (code "81") (name "P3.3V") (class "Default")
      (node (ref "P_TAMPER") (pin "1") (pinfunction "1_1") (pintype "passive"))
      (node (ref "P_USB") (pin "2") (pinfunction "2_2") (pintype "passive"))
      (node (ref "R17B") (pin "2") (pinfunction "2_2") (pintype "passive"))
      (node (ref "R23B") (pin "2") (pinfunction "2_2") (pintype "passive"))
      (node (ref "R25B") (pin "2") (pinfunction "2_2") (pintype "passive"))
    )
    (net (code "82") (name "P3.3V_DELAYED") (class "Default")
      (node (ref "P10B") (pin "2") (pinfunction "2_2") (pintype "passive"))
      (node (ref "P_EXT") (pin "1") (pinfunction "1_1") (pintype "passive"))
      (node (ref "P_SATA") (pin "1") (pinfunction "1_1") (pintype "passive"))
      (node (ref "R13B") (pin "2") (pinfunction "2_2") (pintype "passive"))
      (node (ref "R14B") (pin "2") (pinfunction "2_2") (pintype "passive"))
      (node (ref "R15B") (pin "2") (pinfunction "2_2") (pintype "passive"))
      (node (ref "R16B") (pin "2") (pinfunction "2_2") (pintype "passive"))
      (node (ref "R22B") (pin "2") (pinfunction "2_2") (pintype "passive"))
      (node (ref "R35B") (pin "1") (pinfunction "1_1") (pintype "passive"))
      (node (ref "R36B") (pin "1") (pinfunction "1_1") (pintype "passive"))
      (node (ref "R39B") (pin "1") (pinfunction "1_1") (pintype "passive"))
      (node (ref "R41B") (pin "1") (pinfunction "1_1") (pintype "passive"))
      (node (ref "R43B") (pin "1") (pinfunction "1_1") (pintype "passive"))
    )
    (net (code "83") (name "unconnected-(U100A-EIM_D31-PadH21)") (class "Default")
      (node (ref "U100") (pin "H21") (pinfunction "EIM_D31_H21") (pintype "bidirectional"))
    )
    (net (code "84") (name "unconnected-(U100A-EIM_EB0-PadK21)") (class "Default")
      (node (ref "U100") (pin "K21") (pinfunction "EIM_EB0_K21") (pintype "bidirectional"))
    )
    (net (code "85") (name "unconnected-(U100A-EIM_EB1-PadK23)") (class "Default")
      (node (ref "U100") (pin "K23") (pinfunction "EIM_EB1_K23") (pintype "bidirectional"))
    )
    (net (code "86") (name "unconnected-(U100A-EIM_EB3-PadF23)") (class "Default")
      (node (ref "U100") (pin "F23") (pinfunction "EIM_EB3_F23") (pintype "bidirectional"))
    )
  )
)
